# FMC_SFP_ADAPTER_FMC.net
KiCad netlist of a schematic drawn in Altium Designer
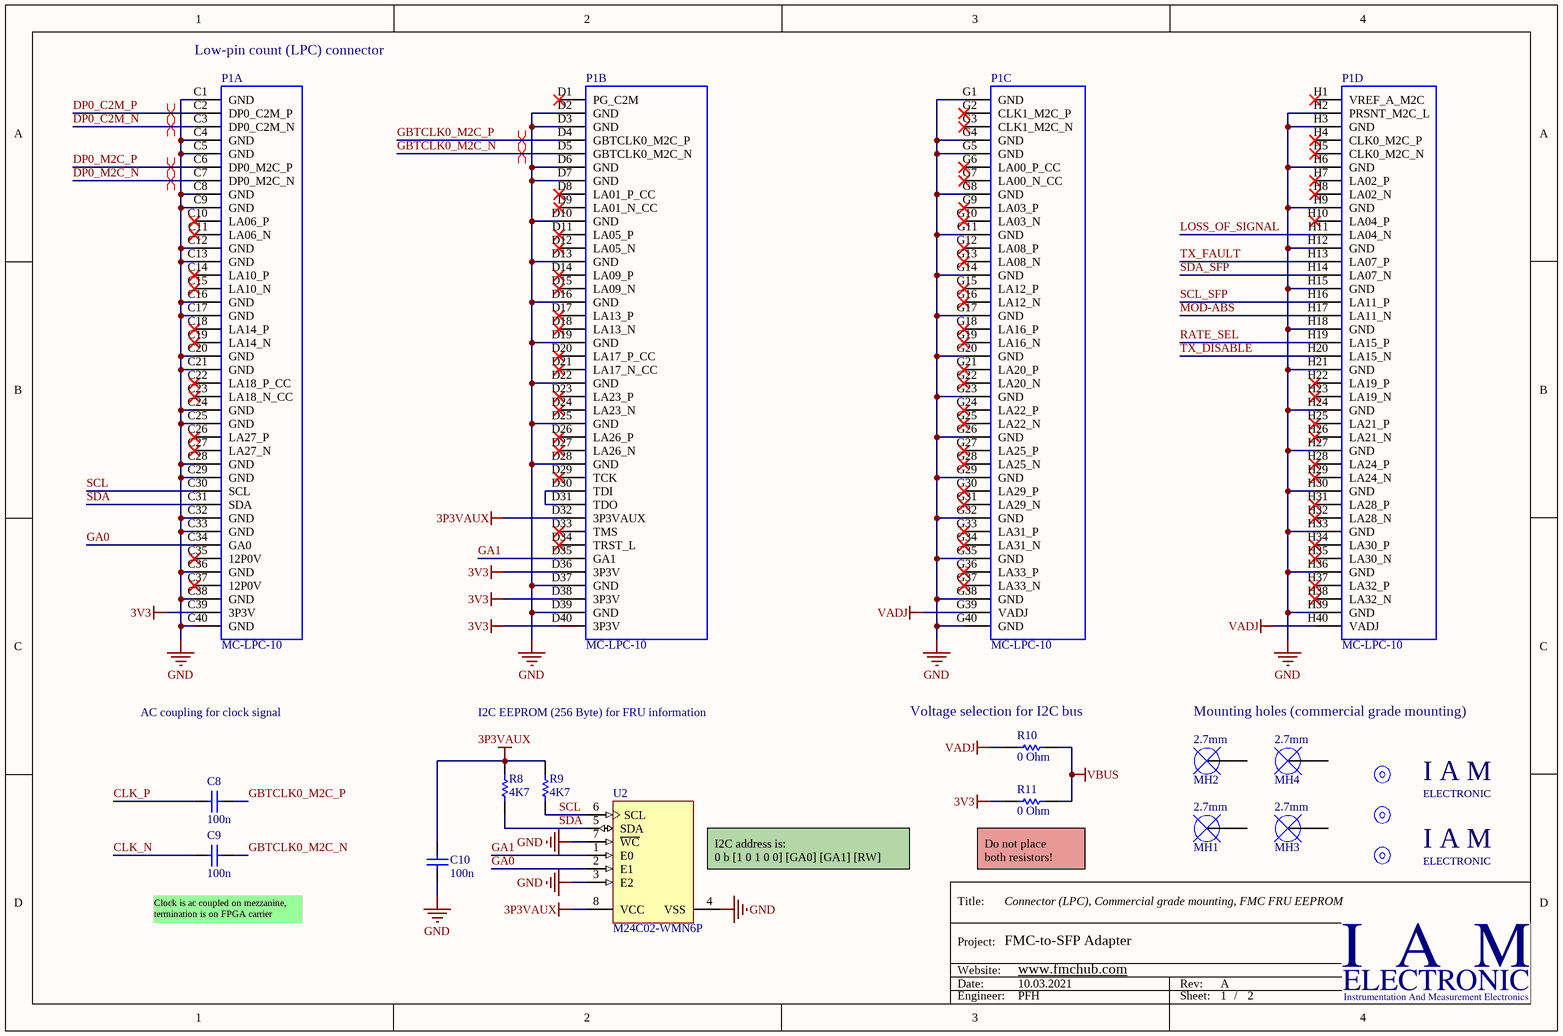
[diagram p0: FMC_SFP_ADAPTER_FMC.SchDoc]

(export (version "E")
  (design (tool "Eeschema 10.0.6"))
  (components
    (comp (ref "C8")
      (value "100n")
      (footprint "CAPC1005X55X25ML05T10")
      (description "Chip Capacitor, 0.1 uF, +/- 10%, 16 V, -55 to 125 degC, 0402 (1005 Metric), RoHS, Tape and Reel")
      (fields (field (name "VOLTAGE") "16V") (field (name "TOLERANCE") "10%"))
      (libsource (lib "Altium Content Vault") (part "CAP-NP-2"))
    )
    (comp (ref "C9")
      (value "100n")
      (footprint "CAPC1005X55X25ML05T10")
      (description "Chip Capacitor, 0.1 uF, +/- 10%, 16 V, -55 to 125 degC, 0402 (1005 Metric), RoHS, Tape and Reel")
      (fields (field (name "VOLTAGE") "16V") (field (name "TOLERANCE") "10%"))
      (libsource (lib "Altium Content Vault") (part "CAP-NP-2"))
    )
    (comp (ref "C10")
      (value "100n")
      (footprint "CAPC1005X55X25ML05T10")
      (description "Chip Capacitor, 0.1 uF, +/- 10%, 16 V, -55 to 125 degC, 0402 (1005 Metric), RoHS, Tape and Reel")
      (fields (field (name "VOLTAGE") "16V") (field (name "TOLERANCE") "10%"))
      (libsource (lib "Altium Content Vault") (part "CAP-NP-2"))
    )
    (comp (ref "FM1")
      (value "1mm")
      (footprint "FIDUCIAL_MARK_ROUND_RING")
      (description "Fiducial mark, width 1mm, clearance 3mm")
      (libsource (lib "VITA_57_FMC") (part "Fiducial_Mark"))
    )
    (comp (ref "FM2")
      (value "1mm")
      (footprint "FIDUCIAL_MARK_ROUND_RING")
      (description "Fiducial mark, width 1mm, clearance 3mm")
      (libsource (lib "VITA_57_FMC") (part "Fiducial_Mark"))
    )
    (comp (ref "FM3")
      (value "1mm")
      (footprint "FIDUCIAL_MARK_ROUND_RING")
      (description "Fiducial mark, width 1mm, clearance 3mm")
      (libsource (lib "VITA_57_FMC") (part "Fiducial_Mark"))
    )
    (comp (ref "MH1")
      (value "2.7mm")
      (footprint "Mounting_Hole_Plated_2.7mm - d3.1mm")
      (description "Mounting hole, hole size 2.7mm")
      (libsource (lib "VITA_57_FMC") (part "Mounting_Hole_2.7mm"))
    )
    (comp (ref "MH2")
      (value "2.7mm")
      (footprint "Mounting_Hole_Plated_2.7mm - d3.1mm")
      (description "Mounting hole, hole size 2.7mm")
      (libsource (lib "VITA_57_FMC") (part "Mounting_Hole_2.7mm"))
    )
    (comp (ref "MH3")
      (value "2.7mm")
      (footprint "Mounting_Hole_Plated_2.7mm-COVERED")
      (description "Mounting hole, hole size 2.7mm")
      (libsource (lib "VITA_57_FMC") (part "Mounting_Hole_2.7mm"))
    )
    (comp (ref "MH4")
      (value "2.7mm")
      (footprint "Mounting_Hole_Plated_2.7mm-COVERED")
      (description "Mounting hole, hole size 2.7mm")
      (libsource (lib "VITA_57_FMC") (part "Mounting_Hole_2.7mm"))
    )
    (comp (ref "P1")
      (value "MC-LPC-10")
      (footprint "ASP-134604-01")
      (description "MC-LPC-10, FMC Low-pin count connector, lead free, 160 I/Os, male, 10 mm mated stack height")
      (fields (field (name "MANUFACTURER") "Samtec") (field (name "PART") "ASP-134604-01"))
      (libsource (lib "VITA_57_FMC") (part "MC-LPC-10"))
    )
    (comp (ref "R8")
      (value "4K7")
      (footprint "RESC1005X40X25ML05T05")
      (description "Chip Resistor, 4.7 KOhm, +/- 1%, 63 mW, -55 to 155 degC, 0402 (1005 Metric), RoHS, Tape and Reel")
      (fields (field (name "PARTNUMBER") "CRCW04024K70FKED") (field (name "TOLERANCE") "1%"))
      (libsource (lib "Altium Content Vault") (part "RES"))
    )
    (comp (ref "R9")
      (value "4K7")
      (footprint "RESC1005X40X25ML05T05")
      (description "Chip Resistor, 4.7 KOhm, +/- 1%, 63 mW, -55 to 155 degC, 0402 (1005 Metric), RoHS, Tape and Reel")
      (fields (field (name "PARTNUMBER") "CRCW04024K70FKED") (field (name "TOLERANCE") "1%"))
      (libsource (lib "Altium Content Vault") (part "RES"))
    )
    (comp (ref "R10")
      (value "0 Ohm")
      (footprint "RESC3116X65X40LL10T20")
      (description "Chip Resistor, 0 Ohm, +/- 5%, -55 to 155 degC, 1206 (3216 Metric), RoHS, Tape and Reel")
      (fields (field (name "MANUFACTURER") "Yageo") (field (name "TOLERANCE") "5%"))
      (libsource (lib "Altium Content Vault") (part "RES-2"))
    )
    (comp (ref "R11")
      (value "0 Ohm")
      (footprint "RESC3116X65X40LL10T20")
      (description "Chip Resistor, 0 Ohm, +/- 5%, -55 to 155 degC, 1206 (3216 Metric), RoHS, Tape and Reel")
      (fields (field (name "MANUFACTURER") "Yageo") (field (name "TOLERANCE") "5%"))
      (libsource (lib "Altium Content Vault") (part "RES-2"))
    )
    (comp (ref "STR1")
      (value "IAM LOGO")
      (footprint "IAM LOGO - LARGE - WWW")
      (description "I A M E L E C T R O N I C - Logo")
      (fields (field (name "MANUFACTURER") "IAM ELECTRONIC") (field (name "PART") "Logo"))
      (libsource (lib "IAM_LOGOS") (part "IAM_LOGO"))
    )
    (comp (ref "STR2")
      (value "IAM LOGO")
      (footprint "IAM LOGO - LARGE - WWW")
      (description "I A M E L E C T R O N I C - Logo")
      (fields (field (name "MANUFACTURER") "IAM ELECTRONIC") (field (name "PART") "Logo"))
      (libsource (lib "IAM_LOGOS") (part "IAM_LOGO"))
    )
    (comp (ref "U2")
      (value "M24C02-WMN6P")
      (footprint "STM-SO-8_D_L")
      (description "2-Kbit Serial I2C Bus EEPROM, 2.5 to 5.5 V, -40 to 85 degC, 8-Pin SOIC, RoHS, Tube")
      (fields (field (name "MANUFACTURER") "STMicroelectronics"))
      (libsource (lib "Altium Content Vault") (part "STM-M24C0X-X-8"))
    )
  )
  (nets
    (net (code "1") (name "/CLK_N") (class "Default")
      (node (ref "C9") (pin "2") (pinfunction "2_2") (pintype "passive"))
    )
    (net (code "2") (name "/CLK_P") (class "Default")
      (node (ref "C8") (pin "2") (pinfunction "2_2") (pintype "passive"))
    )
    (net (code "3") (name "/DP0_C2M_N") (class "Default")
      (node (ref "P1") (pin "C3") (pinfunction "DP0_C2M_N_C3") (pintype "passive"))
    )
    (net (code "4") (name "/DP0_C2M_P") (class "Default")
      (node (ref "P1") (pin "C2") (pinfunction "DP0_C2M_P_C2") (pintype "passive"))
    )
    (net (code "5") (name "/DP0_M2C_N") (class "Default")
      (node (ref "P1") (pin "C7") (pinfunction "DP0_M2C_N_C7") (pintype "passive"))
    )
    (net (code "6") (name "/DP0_M2C_P") (class "Default")
      (node (ref "P1") (pin "C6") (pinfunction "DP0_M2C_P_C6") (pintype "passive"))
    )
    (net (code "7") (name "/GA0") (class "Default")
      (node (ref "P1") (pin "C34") (pinfunction "GA0_C34") (pintype "passive"))
      (node (ref "U2") (pin "2") (pinfunction "E1_2") (pintype "input"))
    )
    (net (code "8") (name "/GA1") (class "Default")
      (node (ref "P1") (pin "D35") (pinfunction "GA1_D35") (pintype "passive"))
      (node (ref "U2") (pin "1") (pinfunction "E0_1") (pintype "input"))
    )
    (net (code "9") (name "/GBTCLK0_M2C_N") (class "Default")
      (node (ref "C9") (pin "1") (pinfunction "1_1") (pintype "passive"))
      (node (ref "P1") (pin "D5") (pinfunction "GBTCLK0_M2C_N_D5") (pintype "passive"))
    )
    (net (code "10") (name "/GBTCLK0_M2C_P") (class "Default")
      (node (ref "C8") (pin "1") (pinfunction "1_1") (pintype "passive"))
      (node (ref "P1") (pin "D4") (pinfunction "GBTCLK0_M2C_P_D4") (pintype "passive"))
    )
    (net (code "11") (name "/LOSS_OF_SIGNAL") (class "Default")
      (node (ref "P1") (pin "H11") (pinfunction "LA04_N_H11") (pintype "passive"))
    )
    (net (code "12") (name "/MOD-ABS") (class "Default")
      (node (ref "P1") (pin "H17") (pinfunction "LA11_N_H17") (pintype "passive"))
    )
    (net (code "13") (name "/RATE_SEL") (class "Default")
      (node (ref "P1") (pin "H19") (pinfunction "LA15_P_H19") (pintype "passive"))
    )
    (net (code "14") (name "/SCL") (class "Default")
      (node (ref "P1") (pin "C30") (pinfunction "SCL_C30") (pintype "passive"))
      (node (ref "R9") (pin "1") (pinfunction "1_1") (pintype "passive"))
      (node (ref "U2") (pin "6") (pinfunction "SCL_6") (pintype "input"))
    )
    (net (code "15") (name "/SCL_SFP") (class "Default")
      (node (ref "P1") (pin "H16") (pinfunction "LA11_P_H16") (pintype "passive"))
    )
    (net (code "16") (name "/SDA") (class "Default")
      (node (ref "P1") (pin "C31") (pinfunction "SDA_C31") (pintype "passive"))
      (node (ref "R8") (pin "1") (pinfunction "1_1") (pintype "passive"))
      (node (ref "U2") (pin "5") (pinfunction "SDA_5") (pintype "bidirectional"))
    )
    (net (code "17") (name "/SDA_SFP") (class "Default")
      (node (ref "P1") (pin "H14") (pinfunction "LA07_N_H14") (pintype "passive"))
    )
    (net (code "18") (name "/TX_DISABLE") (class "Default")
      (node (ref "P1") (pin "H20") (pinfunction "LA15_N_H20") (pintype "passive"))
    )
    (net (code "19") (name "/TX_FAULT") (class "Default")
      (node (ref "P1") (pin "H13") (pinfunction "LA07_P_H13") (pintype "passive"))
    )
    (net (code "20") (name "3P3VAUX") (class "Default")
      (node (ref "C10") (pin "2") (pinfunction "2_2") (pintype "passive"))
      (node (ref "P1") (pin "D32") (pinfunction "3P3VAUX_D32") (pintype "passive"))
      (node (ref "R8") (pin "2") (pinfunction "2_2") (pintype "passive"))
      (node (ref "R9") (pin "2") (pinfunction "2_2") (pintype "passive"))
      (node (ref "U2") (pin "8") (pinfunction "VCC_8") (pintype "power_in"))
    )
    (net (code "21") (name "3V3") (class "Default")
      (node (ref "P1") (pin "C39") (pinfunction "3P3V_C39") (pintype "passive"))
      (node (ref "P1") (pin "D36") (pinfunction "3P3V_D36") (pintype "passive"))
      (node (ref "P1") (pin "D38") (pinfunction "3P3V_D38") (pintype "passive"))
      (node (ref "P1") (pin "D40") (pinfunction "3P3V_D40") (pintype "passive"))
      (node (ref "R11") (pin "1") (pinfunction "1_1") (pintype "passive"))
    )
    (net (code "22") (name "GND") (class "Default")
      (node (ref "C10") (pin "1") (pinfunction "1_1") (pintype "passive"))
      (node (ref "P1") (pin "C1") (pinfunction "GND_C1") (pintype "passive"))
      (node (ref "P1") (pin "C12") (pinfunction "GND_C12") (pintype "passive"))
      (node (ref "P1") (pin "C13") (pinfunction "GND_C13") (pintype "passive"))
      (node (ref "P1") (pin "C16") (pinfunction "GND_C16") (pintype "passive"))
      (node (ref "P1") (pin "C17") (pinfunction "GND_C17") (pintype "passive"))
      (node (ref "P1") (pin "C20") (pinfunction "GND_C20") (pintype "passive"))
      (node (ref "P1") (pin "C21") (pinfunction "GND_C21") (pintype "passive"))
      (node (ref "P1") (pin "C24") (pinfunction "GND_C24") (pintype "passive"))
      (node (ref "P1") (pin "C25") (pinfunction "GND_C25") (pintype "passive"))
      (node (ref "P1") (pin "C28") (pinfunction "GND_C28") (pintype "passive"))
      (node (ref "P1") (pin "C29") (pinfunction "GND_C29") (pintype "passive"))
      (node (ref "P1") (pin "C32") (pinfunction "GND_C32") (pintype "passive"))
      (node (ref "P1") (pin "C33") (pinfunction "GND_C33") (pintype "passive"))
      (node (ref "P1") (pin "C36") (pinfunction "GND_C36") (pintype "passive"))
      (node (ref "P1") (pin "C38") (pinfunction "GND_C38") (pintype "passive"))
      (node (ref "P1") (pin "C4") (pinfunction "GND_C4") (pintype "passive"))
      (node (ref "P1") (pin "C40") (pinfunction "GND_C40") (pintype "passive"))
      (node (ref "P1") (pin "C5") (pinfunction "GND_C5") (pintype "passive"))
      (node (ref "P1") (pin "C8") (pinfunction "GND_C8") (pintype "passive"))
      (node (ref "P1") (pin "C9") (pinfunction "GND_C9") (pintype "passive"))
      (node (ref "P1") (pin "D10") (pinfunction "GND_D10") (pintype "passive"))
      (node (ref "P1") (pin "D13") (pinfunction "GND_D13") (pintype "passive"))
      (node (ref "P1") (pin "D16") (pinfunction "GND_D16") (pintype "passive"))
      (node (ref "P1") (pin "D19") (pinfunction "GND_D19") (pintype "passive"))
      (node (ref "P1") (pin "D2") (pinfunction "GND_D2") (pintype "passive"))
      (node (ref "P1") (pin "D22") (pinfunction "GND_D22") (pintype "passive"))
      (node (ref "P1") (pin "D25") (pinfunction "GND_D25") (pintype "passive"))
      (node (ref "P1") (pin "D28") (pinfunction "GND_D28") (pintype "passive"))
      (node (ref "P1") (pin "D3") (pinfunction "GND_D3") (pintype "passive"))
      (node (ref "P1") (pin "D37") (pinfunction "GND_D37") (pintype "passive"))
      (node (ref "P1") (pin "D39") (pinfunction "GND_D39") (pintype "passive"))
      (node (ref "P1") (pin "D6") (pinfunction "GND_D6") (pintype "passive"))
      (node (ref "P1") (pin "D7") (pinfunction "GND_D7") (pintype "passive"))
      (node (ref "P1") (pin "G1") (pinfunction "GND_G1") (pintype "passive"))
      (node (ref "P1") (pin "G11") (pinfunction "GND_G11") (pintype "passive"))
      (node (ref "P1") (pin "G14") (pinfunction "GND_G14") (pintype "passive"))
      (node (ref "P1") (pin "G17") (pinfunction "GND_G17") (pintype "passive"))
      (node (ref "P1") (pin "G20") (pinfunction "GND_G20") (pintype "passive"))
      (node (ref "P1") (pin "G23") (pinfunction "GND_G23") (pintype "passive"))
      (node (ref "P1") (pin "G26") (pinfunction "GND_G26") (pintype "passive"))
      (node (ref "P1") (pin "G29") (pinfunction "GND_G29") (pintype "passive"))
      (node (ref "P1") (pin "G32") (pinfunction "GND_G32") (pintype "passive"))
      (node (ref "P1") (pin "G35") (pinfunction "GND_G35") (pintype "passive"))
      (node (ref "P1") (pin "G38") (pinfunction "GND_G38") (pintype "passive"))
      (node (ref "P1") (pin "G4") (pinfunction "GND_G4") (pintype "passive"))
      (node (ref "P1") (pin "G40") (pinfunction "GND_G40") (pintype "passive"))
      (node (ref "P1") (pin "G5") (pinfunction "GND_G5") (pintype "passive"))
      (node (ref "P1") (pin "G8") (pinfunction "GND_G8") (pintype "passive"))
      (node (ref "P1") (pin "H12") (pinfunction "GND_H12") (pintype "passive"))
      (node (ref "P1") (pin "H15") (pinfunction "GND_H15") (pintype "passive"))
      (node (ref "P1") (pin "H18") (pinfunction "GND_H18") (pintype "passive"))
      (node (ref "P1") (pin "H2") (pinfunction "PRSNT_M2C_L_H2") (pintype "passive"))
      (node (ref "P1") (pin "H21") (pinfunction "GND_H21") (pintype "passive"))
      (node (ref "P1") (pin "H24") (pinfunction "GND_H24") (pintype "passive"))
      (node (ref "P1") (pin "H27") (pinfunction "GND_H27") (pintype "passive"))
      (node (ref "P1") (pin "H3") (pinfunction "GND_H3") (pintype "passive"))
      (node (ref "P1") (pin "H30") (pinfunction "GND_H30") (pintype "passive"))
      (node (ref "P1") (pin "H33") (pinfunction "GND_H33") (pintype "passive"))
      (node (ref "P1") (pin "H36") (pinfunction "GND_H36") (pintype "passive"))
      (node (ref "P1") (pin "H39") (pinfunction "GND_H39") (pintype "passive"))
      (node (ref "P1") (pin "H6") (pinfunction "GND_H6") (pintype "passive"))
      (node (ref "P1") (pin "H9") (pinfunction "GND_H9") (pintype "passive"))
      (node (ref "U2") (pin "3") (pinfunction "E2_3") (pintype "input"))
      (node (ref "U2") (pin "4") (pinfunction "VSS_4") (pintype "power_in"))
      (node (ref "U2") (pin "7") (pinfunction "~{WC}_7") (pintype "input"))
    )
    (net (code "23") (name "Net-(P1B-TDI)") (class "Default")
      (node (ref "P1") (pin "D30") (pinfunction "TDI_D30") (pintype "passive"))
      (node (ref "P1") (pin "D31") (pinfunction "TDO_D31") (pintype "passive"))
    )
    (net (code "24") (name "VADJ") (class "Default")
      (node (ref "P1") (pin "G39") (pinfunction "VADJ_G39") (pintype "passive"))
      (node (ref "P1") (pin "H40") (pinfunction "VADJ_H40") (pintype "passive"))
      (node (ref "R10") (pin "1") (pinfunction "1_1") (pintype "passive"))
    )
    (net (code "25") (name "VBUS") (class "Default")
      (node (ref "R10") (pin "2") (pinfunction "2_2") (pintype "passive"))
      (node (ref "R11") (pin "2") (pinfunction "2_2") (pintype "passive"))
    )
    (net (code "26") (name "unconnected-(FM1-PadFD0)") (class "Default")
      (node (ref "FM1") (pin "FD0") (pinfunction "FD0_FD0") (pintype "passive"))
    )
    (net (code "27") (name "unconnected-(FM2-PadFD0)") (class "Default")
      (node (ref "FM2") (pin "FD0") (pinfunction "FD0_FD0") (pintype "passive"))
    )
    (net (code "28") (name "unconnected-(FM3-PadFD0)") (class "Default")
      (node (ref "FM3") (pin "FD0") (pinfunction "FD0_FD0") (pintype "passive"))
    )
    (net (code "29") (name "unconnected-(MH1-Pad0)") (class "Default")
      (node (ref "MH1") (pin "0") (pinfunction "0_0") (pintype "passive"))
    )
    (net (code "30") (name "unconnected-(MH2-Pad0)") (class "Default")
      (node (ref "MH2") (pin "0") (pinfunction "0_0") (pintype "passive"))
    )
    (net (code "31") (name "unconnected-(MH3-Pad0)") (class "Default")
      (node (ref "MH3") (pin "0") (pinfunction "0_0") (pintype "passive"))
    )
    (net (code "32") (name "unconnected-(MH4-Pad0)") (class "Default")
      (node (ref "MH4") (pin "0") (pinfunction "0_0") (pintype "passive"))
    )
    (net (code "33") (name "unconnected-(P1A-12P0V-PadC35)") (class "Default")
      (node (ref "P1") (pin "C35") (pinfunction "12P0V_C35") (pintype "passive+no_connect"))
    )
    (net (code "34") (name "unconnected-(P1A-12P0V-PadC37)") (class "Default")
      (node (ref "P1") (pin "C37") (pinfunction "12P0V_C37") (pintype "passive+no_connect"))
    )
    (net (code "35") (name "unconnected-(P1A-LA06_N-PadC11)") (class "Default")
      (node (ref "P1") (pin "C11") (pinfunction "LA06_N_C11") (pintype "passive+no_connect"))
    )
    (net (code "36") (name "unconnected-(P1A-LA06_P-PadC10)") (class "Default")
      (node (ref "P1") (pin "C10") (pinfunction "LA06_P_C10") (pintype "passive+no_connect"))
    )
    (net (code "37") (name "unconnected-(P1A-LA10_N-PadC15)") (class "Default")
      (node (ref "P1") (pin "C15") (pinfunction "LA10_N_C15") (pintype "passive+no_connect"))
    )
    (net (code "38") (name "unconnected-(P1A-LA10_P-PadC14)") (class "Default")
      (node (ref "P1") (pin "C14") (pinfunction "LA10_P_C14") (pintype "passive+no_connect"))
    )
    (net (code "39") (name "unconnected-(P1A-LA14_N-PadC19)") (class "Default")
      (node (ref "P1") (pin "C19") (pinfunction "LA14_N_C19") (pintype "passive+no_connect"))
    )
    (net (code "40") (name "unconnected-(P1A-LA14_P-PadC18)") (class "Default")
      (node (ref "P1") (pin "C18") (pinfunction "LA14_P_C18") (pintype "passive+no_connect"))
    )
    (net (code "41") (name "unconnected-(P1A-LA18_N_CC-PadC23)") (class "Default")
      (node (ref "P1") (pin "C23") (pinfunction "LA18_N_CC_C23") (pintype "passive+no_connect"))
    )
    (net (code "42") (name "unconnected-(P1A-LA18_P_CC-PadC22)") (class "Default")
      (node (ref "P1") (pin "C22") (pinfunction "LA18_P_CC_C22") (pintype "passive+no_connect"))
    )
    (net (code "43") (name "unconnected-(P1A-LA27_N-PadC27)") (class "Default")
      (node (ref "P1") (pin "C27") (pinfunction "LA27_N_C27") (pintype "passive+no_connect"))
    )
    (net (code "44") (name "unconnected-(P1A-LA27_P-PadC26)") (class "Default")
      (node (ref "P1") (pin "C26") (pinfunction "LA27_P_C26") (pintype "passive+no_connect"))
    )
    (net (code "45") (name "unconnected-(P1B-LA01_N_CC-PadD9)") (class "Default")
      (node (ref "P1") (pin "D9") (pinfunction "LA01_N_CC_D9") (pintype "passive+no_connect"))
    )
    (net (code "46") (name "unconnected-(P1B-LA01_P_CC-PadD8)") (class "Default")
      (node (ref "P1") (pin "D8") (pinfunction "LA01_P_CC_D8") (pintype "passive+no_connect"))
    )
    (net (code "47") (name "unconnected-(P1B-LA05_N-PadD12)") (class "Default")
      (node (ref "P1") (pin "D12") (pinfunction "LA05_N_D12") (pintype "passive+no_connect"))
    )
    (net (code "48") (name "unconnected-(P1B-LA05_P-PadD11)") (class "Default")
      (node (ref "P1") (pin "D11") (pinfunction "LA05_P_D11") (pintype "passive+no_connect"))
    )
    (net (code "49") (name "unconnected-(P1B-LA09_N-PadD15)") (class "Default")
      (node (ref "P1") (pin "D15") (pinfunction "LA09_N_D15") (pintype "passive+no_connect"))
    )
    (net (code "50") (name "unconnected-(P1B-LA09_P-PadD14)") (class "Default")
      (node (ref "P1") (pin "D14") (pinfunction "LA09_P_D14") (pintype "passive+no_connect"))
    )
    (net (code "51") (name "unconnected-(P1B-LA13_N-PadD18)") (class "Default")
      (node (ref "P1") (pin "D18") (pinfunction "LA13_N_D18") (pintype "passive+no_connect"))
    )
    (net (code "52") (name "unconnected-(P1B-LA13_P-PadD17)") (class "Default")
      (node (ref "P1") (pin "D17") (pinfunction "LA13_P_D17") (pintype "passive+no_connect"))
    )
    (net (code "53") (name "unconnected-(P1B-LA17_N_CC-PadD21)") (class "Default")
      (node (ref "P1") (pin "D21") (pinfunction "LA17_N_CC_D21") (pintype "passive+no_connect"))
    )
    (net (code "54") (name "unconnected-(P1B-LA17_P_CC-PadD20)") (class "Default")
      (node (ref "P1") (pin "D20") (pinfunction "LA17_P_CC_D20") (pintype "passive+no_connect"))
    )
    (net (code "55") (name "unconnected-(P1B-LA23_N-PadD24)") (class "Default")
      (node (ref "P1") (pin "D24") (pinfunction "LA23_N_D24") (pintype "passive+no_connect"))
    )
    (net (code "56") (name "unconnected-(P1B-LA23_P-PadD23)") (class "Default")
      (node (ref "P1") (pin "D23") (pinfunction "LA23_P_D23") (pintype "passive+no_connect"))
    )
    (net (code "57") (name "unconnected-(P1B-LA26_N-PadD27)") (class "Default")
      (node (ref "P1") (pin "D27") (pinfunction "LA26_N_D27") (pintype "passive+no_connect"))
    )
    (net (code "58") (name "unconnected-(P1B-LA26_P-PadD26)") (class "Default")
      (node (ref "P1") (pin "D26") (pinfunction "LA26_P_D26") (pintype "passive+no_connect"))
    )
    (net (code "59") (name "unconnected-(P1B-PG_C2M-PadD1)") (class "Default")
      (node (ref "P1") (pin "D1") (pinfunction "PG_C2M_D1") (pintype "passive+no_connect"))
    )
    (net (code "60") (name "unconnected-(P1B-TCK-PadD29)") (class "Default")
      (node (ref "P1") (pin "D29") (pinfunction "TCK_D29") (pintype "passive+no_connect"))
    )
    (net (code "61") (name "unconnected-(P1B-TMS-PadD33)") (class "Default")
      (node (ref "P1") (pin "D33") (pinfunction "TMS_D33") (pintype "passive+no_connect"))
    )
    (net (code "62") (name "unconnected-(P1B-TRST_L-PadD34)") (class "Default")
      (node (ref "P1") (pin "D34") (pinfunction "TRST_L_D34") (pintype "passive+no_connect"))
    )
    (net (code "63") (name "unconnected-(P1C-CLK1_M2C_N-PadG3)") (class "Default")
      (node (ref "P1") (pin "G3") (pinfunction "CLK1_M2C_N_G3") (pintype "passive+no_connect"))
    )
    (net (code "64") (name "unconnected-(P1C-CLK1_M2C_P-PadG2)") (class "Default")
      (node (ref "P1") (pin "G2") (pinfunction "CLK1_M2C_P_G2") (pintype "passive+no_connect"))
    )
    (net (code "65") (name "unconnected-(P1C-LA00_N_CC-PadG7)") (class "Default")
      (node (ref "P1") (pin "G7") (pinfunction "LA00_N_CC_G7") (pintype "passive+no_connect"))
    )
    (net (code "66") (name "unconnected-(P1C-LA00_P_CC-PadG6)") (class "Default")
      (node (ref "P1") (pin "G6") (pinfunction "LA00_P_CC_G6") (pintype "passive+no_connect"))
    )
    (net (code "67") (name "unconnected-(P1C-LA03_N-PadG10)") (class "Default")
      (node (ref "P1") (pin "G10") (pinfunction "LA03_N_G10") (pintype "passive+no_connect"))
    )
    (net (code "68") (name "unconnected-(P1C-LA03_P-PadG9)") (class "Default")
      (node (ref "P1") (pin "G9") (pinfunction "LA03_P_G9") (pintype "passive+no_connect"))
    )
    (net (code "69") (name "unconnected-(P1C-LA08_N-PadG13)") (class "Default")
      (node (ref "P1") (pin "G13") (pinfunction "LA08_N_G13") (pintype "passive+no_connect"))
    )
    (net (code "70") (name "unconnected-(P1C-LA08_P-PadG12)") (class "Default")
      (node (ref "P1") (pin "G12") (pinfunction "LA08_P_G12") (pintype "passive+no_connect"))
    )
    (net (code "71") (name "unconnected-(P1C-LA12_N-PadG16)") (class "Default")
      (node (ref "P1") (pin "G16") (pinfunction "LA12_N_G16") (pintype "passive+no_connect"))
    )
    (net (code "72") (name "unconnected-(P1C-LA12_P-PadG15)") (class "Default")
      (node (ref "P1") (pin "G15") (pinfunction "LA12_P_G15") (pintype "passive+no_connect"))
    )
    (net (code "73") (name "unconnected-(P1C-LA16_N-PadG19)") (class "Default")
      (node (ref "P1") (pin "G19") (pinfunction "LA16_N_G19") (pintype "passive+no_connect"))
    )
    (net (code "74") (name "unconnected-(P1C-LA16_P-PadG18)") (class "Default")
      (node (ref "P1") (pin "G18") (pinfunction "LA16_P_G18") (pintype "passive+no_connect"))
    )
    (net (code "75") (name "unconnected-(P1C-LA20_N-PadG22)") (class "Default")
      (node (ref "P1") (pin "G22") (pinfunction "LA20_N_G22") (pintype "passive+no_connect"))
    )
    (net (code "76") (name "unconnected-(P1C-LA20_P-PadG21)") (class "Default")
      (node (ref "P1") (pin "G21") (pinfunction "LA20_P_G21") (pintype "passive+no_connect"))
    )
    (net (code "77") (name "unconnected-(P1C-LA22_N-PadG25)") (class "Default")
      (node (ref "P1") (pin "G25") (pinfunction "LA22_N_G25") (pintype "passive+no_connect"))
    )
    (net (code "78") (name "unconnected-(P1C-LA22_P-PadG24)") (class "Default")
      (node (ref "P1") (pin "G24") (pinfunction "LA22_P_G24") (pintype "passive+no_connect"))
    )
    (net (code "79") (name "unconnected-(P1C-LA25_N-PadG28)") (class "Default")
      (node (ref "P1") (pin "G28") (pinfunction "LA25_N_G28") (pintype "passive+no_connect"))
    )
    (net (code "80") (name "unconnected-(P1C-LA25_P-PadG27)") (class "Default")
      (node (ref "P1") (pin "G27") (pinfunction "LA25_P_G27") (pintype "passive+no_connect"))
    )
    (net (code "81") (name "unconnected-(P1C-LA29_N-PadG31)") (class "Default")
      (node (ref "P1") (pin "G31") (pinfunction "LA29_N_G31") (pintype "passive+no_connect"))
    )
    (net (code "82") (name "unconnected-(P1C-LA29_P-PadG30)") (class "Default")
      (node (ref "P1") (pin "G30") (pinfunction "LA29_P_G30") (pintype "passive+no_connect"))
    )
    (net (code "83") (name "unconnected-(P1C-LA31_N-PadG34)") (class "Default")
      (node (ref "P1") (pin "G34") (pinfunction "LA31_N_G34") (pintype "passive+no_connect"))
    )
    (net (code "84") (name "unconnected-(P1C-LA31_P-PadG33)") (class "Default")
      (node (ref "P1") (pin "G33") (pinfunction "LA31_P_G33") (pintype "passive+no_connect"))
    )
    (net (code "85") (name "unconnected-(P1C-LA33_N-PadG37)") (class "Default")
      (node (ref "P1") (pin "G37") (pinfunction "LA33_N_G37") (pintype "passive+no_connect"))
    )
    (net (code "86") (name "unconnected-(P1C-LA33_P-PadG36)") (class "Default")
      (node (ref "P1") (pin "G36") (pinfunction "LA33_P_G36") (pintype "passive+no_connect"))
    )
    (net (code "87") (name "unconnected-(P1D-CLK0_M2C_N-PadH5)") (class "Default")
      (node (ref "P1") (pin "H5") (pinfunction "CLK0_M2C_N_H5") (pintype "passive+no_connect"))
    )
    (net (code "88") (name "unconnected-(P1D-CLK0_M2C_P-PadH4)") (class "Default")
      (node (ref "P1") (pin "H4") (pinfunction "CLK0_M2C_P_H4") (pintype "passive+no_connect"))
    )
    (net (code "89") (name "unconnected-(P1D-LA02_N-PadH8)") (class "Default")
      (node (ref "P1") (pin "H8") (pinfunction "LA02_N_H8") (pintype "passive+no_connect"))
    )
    (net (code "90") (name "unconnected-(P1D-LA02_P-PadH7)") (class "Default")
      (node (ref "P1") (pin "H7") (pinfunction "LA02_P_H7") (pintype "passive+no_connect"))
    )
    (net (code "91") (name "unconnected-(P1D-LA04_P-PadH10)") (class "Default")
      (node (ref "P1") (pin "H10") (pinfunction "LA04_P_H10") (pintype "passive+no_connect"))
    )
    (net (code "92") (name "unconnected-(P1D-LA19_N-PadH23)") (class "Default")
      (node (ref "P1") (pin "H23") (pinfunction "LA19_N_H23") (pintype "passive+no_connect"))
    )
    (net (code "93") (name "unconnected-(P1D-LA19_P-PadH22)") (class "Default")
      (node (ref "P1") (pin "H22") (pinfunction "LA19_P_H22") (pintype "passive+no_connect"))
    )
    (net (code "94") (name "unconnected-(P1D-LA21_N-PadH26)") (class "Default")
      (node (ref "P1") (pin "H26") (pinfunction "LA21_N_H26") (pintype "passive+no_connect"))
    )
    (net (code "95") (name "unconnected-(P1D-LA21_P-PadH25)") (class "Default")
      (node (ref "P1") (pin "H25") (pinfunction "LA21_P_H25") (pintype "passive+no_connect"))
    )
    (net (code "96") (name "unconnected-(P1D-LA24_N-PadH29)") (class "Default")
      (node (ref "P1") (pin "H29") (pinfunction "LA24_N_H29") (pintype "passive+no_connect"))
    )
    (net (code "97") (name "unconnected-(P1D-LA24_P-PadH28)") (class "Default")
      (node (ref "P1") (pin "H28") (pinfunction "LA24_P_H28") (pintype "passive+no_connect"))
    )
    (net (code "98") (name "unconnected-(P1D-LA28_N-PadH32)") (class "Default")
      (node (ref "P1") (pin "H32") (pinfunction "LA28_N_H32") (pintype "passive+no_connect"))
    )
    (net (code "99") (name "unconnected-(P1D-LA28_P-PadH31)") (class "Default")
      (node (ref "P1") (pin "H31") (pinfunction "LA28_P_H31") (pintype "passive+no_connect"))
    )
    (net (code "100") (name "unconnected-(P1D-LA30_N-PadH35)") (class "Default")
      (node (ref "P1") (pin "H35") (pinfunction "LA30_N_H35") (pintype "passive+no_connect"))
    )
    (net (code "101") (name "unconnected-(P1D-LA30_P-PadH34)") (class "Default")
      (node (ref "P1") (pin "H34") (pinfunction "LA30_P_H34") (pintype "passive+no_connect"))
    )
    (net (code "102") (name "unconnected-(P1D-LA32_N-PadH38)") (class "Default")
      (node (ref "P1") (pin "H38") (pinfunction "LA32_N_H38") (pintype "passive+no_connect"))
    )
    (net (code "103") (name "unconnected-(P1D-LA32_P-PadH37)") (class "Default")
      (node (ref "P1") (pin "H37") (pinfunction "LA32_P_H37") (pintype "passive+no_connect"))
    )
    (net (code "104") (name "unconnected-(P1D-VREF_A_M2C-PadH1)") (class "Default")
      (node (ref "P1") (pin "H1") (pinfunction "VREF_A_M2C_H1") (pintype "passive+no_connect"))
    )
  )
)
